# Encoder.net
KiCad netlist of a schematic drawn in Altium Designer
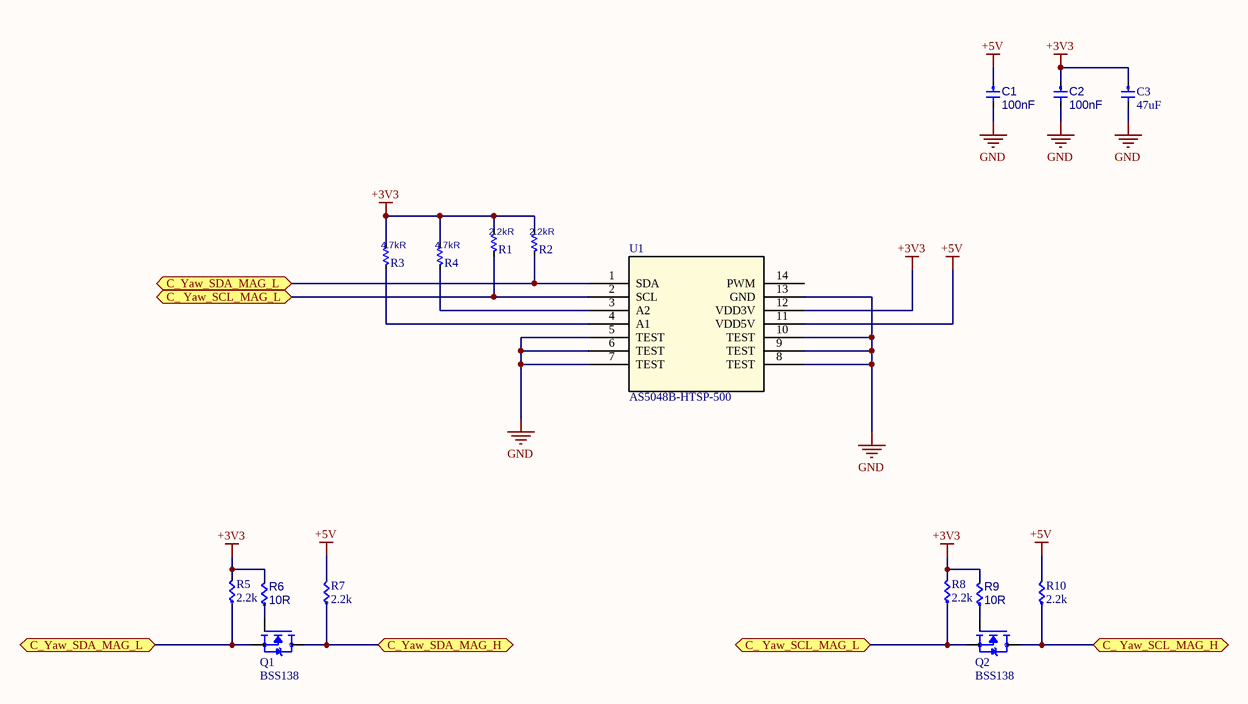
[diagram p0: Encoder.SchDoc]

(export (version "E")
  (design (tool "Eeschema 10.0.6"))
  (components
    (comp (ref "C1")
      (value "C0603C104M5RACTU")
      (footprint "CAP0603")
      (description "CAP CER 0.1UF 50V X7R 0603")
      (fields (field (name "TOLERANCE") "20%") (field (name "CAPACITANCE") "100nF"))
      (libsource (lib "rtr") (part "CMP-00691-1"))
    )
    (comp (ref "C2")
      (value "C0603C104M5RACTU")
      (footprint "CAP0603")
      (description "CAP CER 0.1UF 50V X7R 0603")
      (fields (field (name "TOLERANCE") "20%") (field (name "CAPACITANCE") "100nF"))
      (libsource (lib "rtr") (part "CMP-00691-1"))
    )
    (comp (ref "C3")
      (value "CL21A476MQYNNNE")
      (footprint "CAP0805")
      (description "CAP CER 47UF 6.3V X5R 0805")
      (fields (field (name "TOLERANCE") "20%") (field (name "CAPACITANCE") "47uF"))
      (libsource (lib "rtr") (part "885012107014"))
    )
    (comp (ref "Q1")
      (value "BSS138")
      (footprint "BSS138")
      (description "N-Channel 50 V 220mA (Ta) 350mW (Ta) Surface Mount SOT-23-3")
      (fields (field (name "MF") "onsemi"))
      (libsource (lib "Sbus to Uart") (part "BSS138"))
    )
    (comp (ref "Q2")
      (value "BSS138")
      (footprint "BSS138")
      (description "N-Channel 50 V 220mA (Ta) 350mW (Ta) Surface Mount SOT-23-3")
      (fields (field (name "MF") "onsemi"))
      (libsource (lib "Sbus to Uart") (part "BSS138"))
    )
    (comp (ref "R1")
      (value "2.2kR")
      (footprint "RES0603")
      (description "RES 0805")
      (fields (field (name "MP") "add later") (field (name "Comment") "RES0603"))
      (libsource (lib "RTR") (part "RES0603"))
    )
    (comp (ref "R2")
      (value "2.2kR")
      (footprint "RES0603")
      (description "RES 0805")
      (fields (field (name "MP") "add later") (field (name "Comment") "RES0603"))
      (libsource (lib "RTR") (part "RES0603"))
    )
    (comp (ref "R3")
      (value "4.7kR")
      (footprint "RES0603")
      (description "RES 0805")
      (fields (field (name "MP") "add later") (field (name "Comment") "RES0603"))
      (libsource (lib "RTR") (part "RES0603"))
    )
    (comp (ref "R4")
      (value "4.7kR")
      (footprint "RES0603")
      (description "RES 0805")
      (fields (field (name "MP") "add later") (field (name "Comment") "RES0603"))
      (libsource (lib "RTR") (part "RES0603"))
    )
    (comp (ref "R5")
      (value "2.2k")
      (footprint "RES0603")
      (description "Res Thick Film 0603 2.2K Ohm 1% 0.1W(1/10W) +/-100ppm/C Epoxy Pad SMD T/R")
      (fields
        (field (name "MANUFACTURER") "Yageo Group")
        (field (name "MANUFACTURER PART NUMBER") "RC0603FR-072K2L")
      )
      (libsource (lib "Yaw-Ofil") (part "RC0603FR-072K2L"))
    )
    (comp (ref "R6")
      (value "MCR03EZPJ100")
      (footprint "RES0603")
      (description "RES SMD 10 OHM 5% 1/10W 0603")
      (fields (field (name "TOLERANCE") "5%") (field (name "RESISTANCE") "10R"))
      (libsource (lib "JetsonNX_CSI") (part "CMP-01078-4"))
    )
    (comp (ref "R7")
      (value "2.2k")
      (footprint "RES0603")
      (description "Res Thick Film 0603 2.2K Ohm 1% 0.1W(1/10W) +/-100ppm/C Epoxy Pad SMD T/R")
      (fields
        (field (name "MANUFACTURER") "Yageo Group")
        (field (name "MANUFACTURER PART NUMBER") "RC0603FR-072K2L")
      )
      (libsource (lib "Yaw-Ofil") (part "RC0603FR-072K2L"))
    )
    (comp (ref "R8")
      (value "2.2k")
      (footprint "RES0603")
      (description "Res Thick Film 0603 2.2K Ohm 1% 0.1W(1/10W) +/-100ppm/C Epoxy Pad SMD T/R")
      (fields
        (field (name "MANUFACTURER") "Yageo Group")
        (field (name "MANUFACTURER PART NUMBER") "RC0603FR-072K2L")
      )
      (libsource (lib "Yaw-Ofil") (part "RC0603FR-072K2L"))
    )
    (comp (ref "R9")
      (value "MCR03EZPJ100")
      (footprint "RES0603")
      (description "RES SMD 10 OHM 5% 1/10W 0603")
      (fields (field (name "TOLERANCE") "5%") (field (name "RESISTANCE") "10R"))
      (libsource (lib "JetsonNX_CSI") (part "CMP-01078-4"))
    )
    (comp (ref "R10")
      (value "2.2k")
      (footprint "RES0603")
      (description "Res Thick Film 0603 2.2K Ohm 1% 0.1W(1/10W) +/-100ppm/C Epoxy Pad SMD T/R")
      (fields
        (field (name "MANUFACTURER") "Yageo Group")
        (field (name "MANUFACTURER PART NUMBER") "RC0603FR-072K2L")
      )
      (libsource (lib "Yaw-Ofil") (part "RC0603FR-072K2L"))
    )
    (comp (ref "U1")
      (value "AS5048B-HTSP-500")
      (footprint "AS5048B-HTSP-500")
      (description "No Description Available")
      (libsource (lib "STM32H743VIT6") (part "AS5048B-HTSP-500"))
    )
  )
  (nets
    (net (code "1") (name "+3V3") (class "Default")
      (node (ref "C2") (pin "1") (pinfunction "1_1") (pintype "passive"))
      (node (ref "C3") (pin "1") (pinfunction "1_1") (pintype "passive"))
      (node (ref "R1") (pin "1") (pinfunction "1_1") (pintype "passive"))
      (node (ref "R2") (pin "1") (pinfunction "1_1") (pintype "passive"))
      (node (ref "R3") (pin "1") (pinfunction "1_1") (pintype "passive"))
      (node (ref "R4") (pin "1") (pinfunction "1_1") (pintype "passive"))
      (node (ref "R5") (pin "2") (pinfunction "2_2") (pintype "passive"))
      (node (ref "R6") (pin "2") (pinfunction "2_2") (pintype "passive"))
      (node (ref "R8") (pin "2") (pinfunction "2_2") (pintype "passive"))
      (node (ref "R9") (pin "2") (pinfunction "2_2") (pintype "passive"))
      (node (ref "U1") (pin "12") (pinfunction "VDD3V_12") (pintype "passive"))
    )
    (net (code "2") (name "+5V") (class "Default")
      (node (ref "C1") (pin "1") (pinfunction "1_1") (pintype "passive"))
      (node (ref "R10") (pin "2") (pinfunction "2_2") (pintype "passive"))
      (node (ref "R7") (pin "2") (pinfunction "2_2") (pintype "passive"))
      (node (ref "U1") (pin "11") (pinfunction "VDD5V_11") (pintype "passive"))
    )
    (net (code "3") (name "/C_ Yaw_SCL_MAG_H") (class "Default")
      (node (ref "Q2") (pin "3") (pinfunction "D_3") (pintype "passive"))
      (node (ref "R10") (pin "1") (pinfunction "1_1") (pintype "passive"))
    )
    (net (code "4") (name "/C_ Yaw_SCL_MAG_L") (class "Default")
      (node (ref "Q2") (pin "2") (pinfunction "S_2") (pintype "passive"))
      (node (ref "R1") (pin "2") (pinfunction "2_2") (pintype "passive"))
      (node (ref "R8") (pin "1") (pinfunction "1_1") (pintype "passive"))
      (node (ref "U1") (pin "2") (pinfunction "SCL_2") (pintype "passive"))
    )
    (net (code "5") (name "/C_Yaw_SDA_MAG_H") (class "Default")
      (node (ref "Q1") (pin "3") (pinfunction "D_3") (pintype "passive"))
      (node (ref "R7") (pin "1") (pinfunction "1_1") (pintype "passive"))
    )
    (net (code "6") (name "/C_Yaw_SDA_MAG_L") (class "Default")
      (node (ref "Q1") (pin "2") (pinfunction "S_2") (pintype "passive"))
      (node (ref "R2") (pin "2") (pinfunction "2_2") (pintype "passive"))
      (node (ref "R5") (pin "1") (pinfunction "1_1") (pintype "passive"))
      (node (ref "U1") (pin "1") (pinfunction "SDA_1") (pintype "passive"))
    )
    (net (code "7") (name "GND") (class "Default")
      (node (ref "C1") (pin "2") (pinfunction "2_2") (pintype "passive"))
      (node (ref "C2") (pin "2") (pinfunction "2_2") (pintype "passive"))
      (node (ref "C3") (pin "2") (pinfunction "2_2") (pintype "passive"))
      (node (ref "U1") (pin "10") (pinfunction "TEST_10") (pintype "passive"))
      (node (ref "U1") (pin "13") (pinfunction "GND_13") (pintype "passive"))
      (node (ref "U1") (pin "5") (pinfunction "TEST_5") (pintype "passive"))
      (node (ref "U1") (pin "6") (pinfunction "TEST_6") (pintype "passive"))
      (node (ref "U1") (pin "7") (pinfunction "TEST_7") (pintype "passive"))
      (node (ref "U1") (pin "8") (pinfunction "TEST_8") (pintype "passive"))
      (node (ref "U1") (pin "9") (pinfunction "TEST_9") (pintype "passive"))
    )
    (net (code "8") (name "Net-(Q1-G)") (class "Default")
      (node (ref "Q1") (pin "1") (pinfunction "G_1") (pintype "passive"))
      (node (ref "R6") (pin "1") (pinfunction "1_1") (pintype "passive"))
    )
    (net (code "9") (name "Net-(Q2-G)") (class "Default")
      (node (ref "Q2") (pin "1") (pinfunction "G_1") (pintype "passive"))
      (node (ref "R9") (pin "1") (pinfunction "1_1") (pintype "passive"))
    )
    (net (code "10") (name "Net-(U1-A1)") (class "Default")
      (node (ref "R3") (pin "2") (pinfunction "2_2") (pintype "passive"))
      (node (ref "U1") (pin "4") (pinfunction "A1_4") (pintype "passive"))
    )
    (net (code "11") (name "Net-(U1-A2)") (class "Default")
      (node (ref "R4") (pin "2") (pinfunction "2_2") (pintype "passive"))
      (node (ref "U1") (pin "3") (pinfunction "A2_3") (pintype "passive"))
    )
    (net (code "12") (name "unconnected-(U1-PWM-Pad14)") (class "Default")
      (node (ref "U1") (pin "14") (pinfunction "PWM_14") (pintype "passive"))
    )
  )
)
